# DRV8840_pcbway_optimized.net
KiCad netlist of a schematic drawn in EAGLE
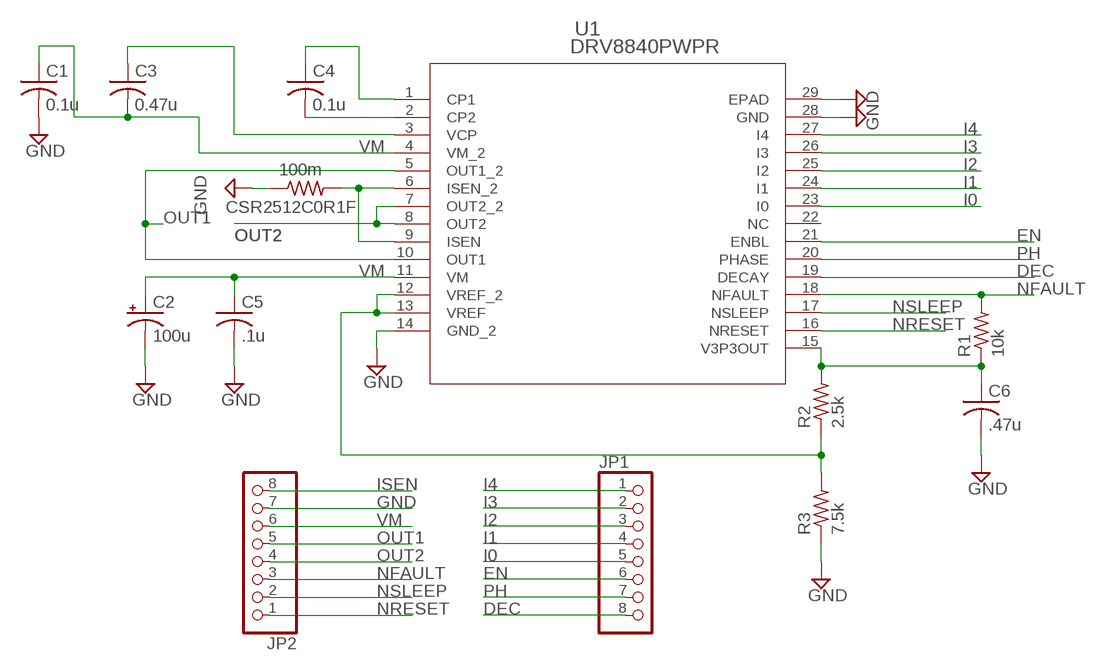
[diagram p0: schematic, sheet 1]

(export (version "E")
  (design (tool "Eeschema 10.0.6"))
  (components
    (comp (ref "C1")
      (value "0.1u")
      (footprint "eagle-import:C025-024X044")
      (libsource (lib "eagle-import") (part "C-US025-024X044"))
    )
    (comp (ref "C2")
      (value "100u")
      (footprint "eagle-import:E2,5-6")
      (libsource (lib "eagle-import") (part "CPOL-USE2.5-6"))
    )
    (comp (ref "C3")
      (value "0.47u")
      (footprint "eagle-import:C1206")
      (libsource (lib "eagle-import") (part "C-USC1206"))
    )
    (comp (ref "C4")
      (value "0.1u")
      (footprint "eagle-import:C1206")
      (libsource (lib "eagle-import") (part "C-USC1206"))
    )
    (comp (ref "C5")
      (value ".1u")
      (footprint "eagle-import:C025-024X044")
      (libsource (lib "eagle-import") (part "C-US025-024X044"))
    )
    (comp (ref "C6")
      (value ".47u")
      (footprint "eagle-import:C025-024X044")
      (libsource (lib "eagle-import") (part "C-US025-024X044"))
    )
    (comp (ref "CSR2512C0R1F")
      (value "100m")
      (footprint "eagle-import:R2512")
      (libsource (lib "eagle-import") (part "R-US_R2512"))
    )
    (comp (ref "JP1")
      (value "PINHD-1X8")
      (footprint "eagle-import:1X08")
      (libsource (lib "eagle-import") (part "PINHD-1X8"))
    )
    (comp (ref "JP2")
      (value "PINHD-1X8")
      (footprint "eagle-import:1X08")
      (libsource (lib "eagle-import") (part "PINHD-1X8"))
    )
    (comp (ref "R1")
      (value "10k")
      (footprint "eagle-import:0204V")
      (libsource (lib "eagle-import") (part "R-US_0204/2V"))
    )
    (comp (ref "R2")
      (value "2.5k")
      (footprint "eagle-import:0207_10")
      (libsource (lib "eagle-import") (part "R-US_0207/10"))
    )
    (comp (ref "R3")
      (value "7.5k")
      (footprint "eagle-import:0207_10")
      (libsource (lib "eagle-import") (part "R-US_0207/10"))
    )
    (comp (ref "U1")
      (value "DRV8840PWPR")
      (footprint "eagle-import:PWP28_5P18X3P1")
      (libsource (lib "eagle-import") (part "DRV8840PWPR"))
    )
  )
  (nets
    (net (code "1") (name "/DEC") (class "Default")
      (node (ref "JP1") (pin "8") (pinfunction "8_8") (pintype "passive"))
      (node (ref "U1") (pin "19") (pinfunction "DECAY_19") (pintype "input"))
    )
    (net (code "2") (name "/EN") (class "Default")
      (node (ref "JP1") (pin "6") (pinfunction "6_6") (pintype "passive"))
      (node (ref "U1") (pin "21") (pinfunction "ENBL_21") (pintype "input"))
    )
    (net (code "3") (name "/I0") (class "Default")
      (node (ref "JP1") (pin "5") (pinfunction "5_5") (pintype "passive"))
      (node (ref "U1") (pin "23") (pinfunction "I0_23") (pintype "input"))
    )
    (net (code "4") (name "/I1") (class "Default")
      (node (ref "JP1") (pin "4") (pinfunction "4_4") (pintype "passive"))
      (node (ref "U1") (pin "24") (pinfunction "I1_24") (pintype "input"))
    )
    (net (code "5") (name "/I2") (class "Default")
      (node (ref "JP1") (pin "3") (pinfunction "3_3") (pintype "passive"))
      (node (ref "U1") (pin "25") (pinfunction "I2_25") (pintype "input"))
    )
    (net (code "6") (name "/I3") (class "Default")
      (node (ref "JP1") (pin "2") (pinfunction "2_2") (pintype "passive"))
      (node (ref "U1") (pin "26") (pinfunction "I3_26") (pintype "input"))
    )
    (net (code "7") (name "/I4") (class "Default")
      (node (ref "JP1") (pin "1") (pinfunction "1_1") (pintype "passive"))
      (node (ref "U1") (pin "27") (pinfunction "I4_27") (pintype "input"))
    )
    (net (code "8") (name "/ISEN") (class "Default")
      (node (ref "CSR2512C0R1F") (pin "2") (pinfunction "2_2") (pintype "passive"))
      (node (ref "JP2") (pin "8") (pinfunction "8_8") (pintype "passive"))
      (node (ref "U1") (pin "6") (pinfunction "ISEN_2_6") (pintype "bidirectional"))
      (node (ref "U1") (pin "9") (pinfunction "ISEN_9") (pintype "bidirectional"))
    )
    (net (code "9") (name "/NFAULT") (class "Default")
      (node (ref "JP2") (pin "3") (pinfunction "3_3") (pintype "passive"))
      (node (ref "R1") (pin "2") (pinfunction "2_2") (pintype "passive"))
      (node (ref "U1") (pin "18") (pinfunction "NFAULT_18") (pintype "output"))
    )
    (net (code "10") (name "/NRESET") (class "Default")
      (node (ref "JP2") (pin "1") (pinfunction "1_1") (pintype "passive"))
      (node (ref "U1") (pin "16") (pinfunction "NRESET_16") (pintype "input"))
    )
    (net (code "11") (name "/NSLEEP") (class "Default")
      (node (ref "JP2") (pin "2") (pinfunction "2_2") (pintype "passive"))
      (node (ref "U1") (pin "17") (pinfunction "NSLEEP_17") (pintype "input"))
    )
    (net (code "12") (name "/OUT1") (class "Default")
      (node (ref "JP2") (pin "5") (pinfunction "5_5") (pintype "passive"))
      (node (ref "U1") (pin "10") (pinfunction "OUT1_10") (pintype "output"))
      (node (ref "U1") (pin "5") (pinfunction "OUT1_2_5") (pintype "output"))
    )
    (net (code "13") (name "/OUT2") (class "Default")
      (node (ref "JP2") (pin "4") (pinfunction "4_4") (pintype "passive"))
      (node (ref "U1") (pin "7") (pinfunction "OUT2_2_7") (pintype "output"))
      (node (ref "U1") (pin "8") (pinfunction "OUT2_8") (pintype "output"))
    )
    (net (code "14") (name "/PH") (class "Default")
      (node (ref "JP1") (pin "7") (pinfunction "7_7") (pintype "passive"))
      (node (ref "U1") (pin "20") (pinfunction "PHASE_20") (pintype "input"))
    )
    (net (code "15") (name "/VM") (class "Default")
      (node (ref "C1") (pin "1") (pinfunction "1_1") (pintype "passive"))
      (node (ref "C2") (pin "+") (pinfunction "+_+") (pintype "passive"))
      (node (ref "C3") (pin "2") (pinfunction "2_2") (pintype "passive"))
      (node (ref "C5") (pin "1") (pinfunction "1_1") (pintype "passive"))
      (node (ref "JP2") (pin "6") (pinfunction "6_6") (pintype "passive"))
      (node (ref "U1") (pin "11") (pinfunction "VM_11") (pintype "power_in"))
      (node (ref "U1") (pin "4") (pinfunction "VM_2_4") (pintype "power_in"))
    )
    (net (code "16") (name "GND") (class "Default")
      (node (ref "C1") (pin "2") (pinfunction "2_2") (pintype "passive"))
      (node (ref "C2") (pin "-") (pinfunction "-_-") (pintype "passive"))
      (node (ref "C5") (pin "2") (pinfunction "2_2") (pintype "passive"))
      (node (ref "C6") (pin "2") (pinfunction "2_2") (pintype "passive"))
      (node (ref "CSR2512C0R1F") (pin "1") (pinfunction "1_1") (pintype "passive"))
      (node (ref "JP2") (pin "7") (pinfunction "7_7") (pintype "passive"))
      (node (ref "R3") (pin "1") (pinfunction "1_1") (pintype "passive"))
      (node (ref "U1") (pin "14") (pinfunction "GND_2_14") (pintype "power_in"))
      (node (ref "U1") (pin "28") (pinfunction "GND_28") (pintype "power_in"))
      (node (ref "U1") (pin "29") (pinfunction "EPAD_29") (pintype "passive"))
    )
    (net (code "17") (name "Net-(U1-CP1)") (class "Default")
      (node (ref "C4") (pin "1") (pinfunction "1_1") (pintype "passive"))
      (node (ref "U1") (pin "1") (pinfunction "CP1_1") (pintype "bidirectional"))
    )
    (net (code "18") (name "Net-(U1-CP2)") (class "Default")
      (node (ref "C4") (pin "2") (pinfunction "2_2") (pintype "passive"))
      (node (ref "U1") (pin "2") (pinfunction "CP2_2") (pintype "bidirectional"))
    )
    (net (code "19") (name "Net-(U1-V3P3OUT)") (class "Default")
      (node (ref "C6") (pin "1") (pinfunction "1_1") (pintype "passive"))
      (node (ref "R1") (pin "1") (pinfunction "1_1") (pintype "passive"))
      (node (ref "R2") (pin "2") (pinfunction "2_2") (pintype "passive"))
      (node (ref "U1") (pin "15") (pinfunction "V3P3OUT_15") (pintype "output"))
    )
    (net (code "20") (name "Net-(U1-VCP)") (class "Default")
      (node (ref "C3") (pin "1") (pinfunction "1_1") (pintype "passive"))
      (node (ref "U1") (pin "3") (pinfunction "VCP_3") (pintype "bidirectional"))
    )
    (net (code "21") (name "Net-(U1-VREF)") (class "Default")
      (node (ref "R2") (pin "1") (pinfunction "1_1") (pintype "passive"))
      (node (ref "R3") (pin "2") (pinfunction "2_2") (pintype "passive"))
      (node (ref "U1") (pin "12") (pinfunction "VREF_2_12") (pintype "input"))
      (node (ref "U1") (pin "13") (pinfunction "VREF_13") (pintype "input"))
    )
    (net (code "22") (name "unconnected-(U1-NC-Pad22)") (class "Default")
      (node (ref "U1") (pin "22") (pinfunction "NC_22") (pintype "passive"))
    )
  )
)
